# KUBODriver_DC.net
KiCad netlist of a schematic drawn in Altium Designer
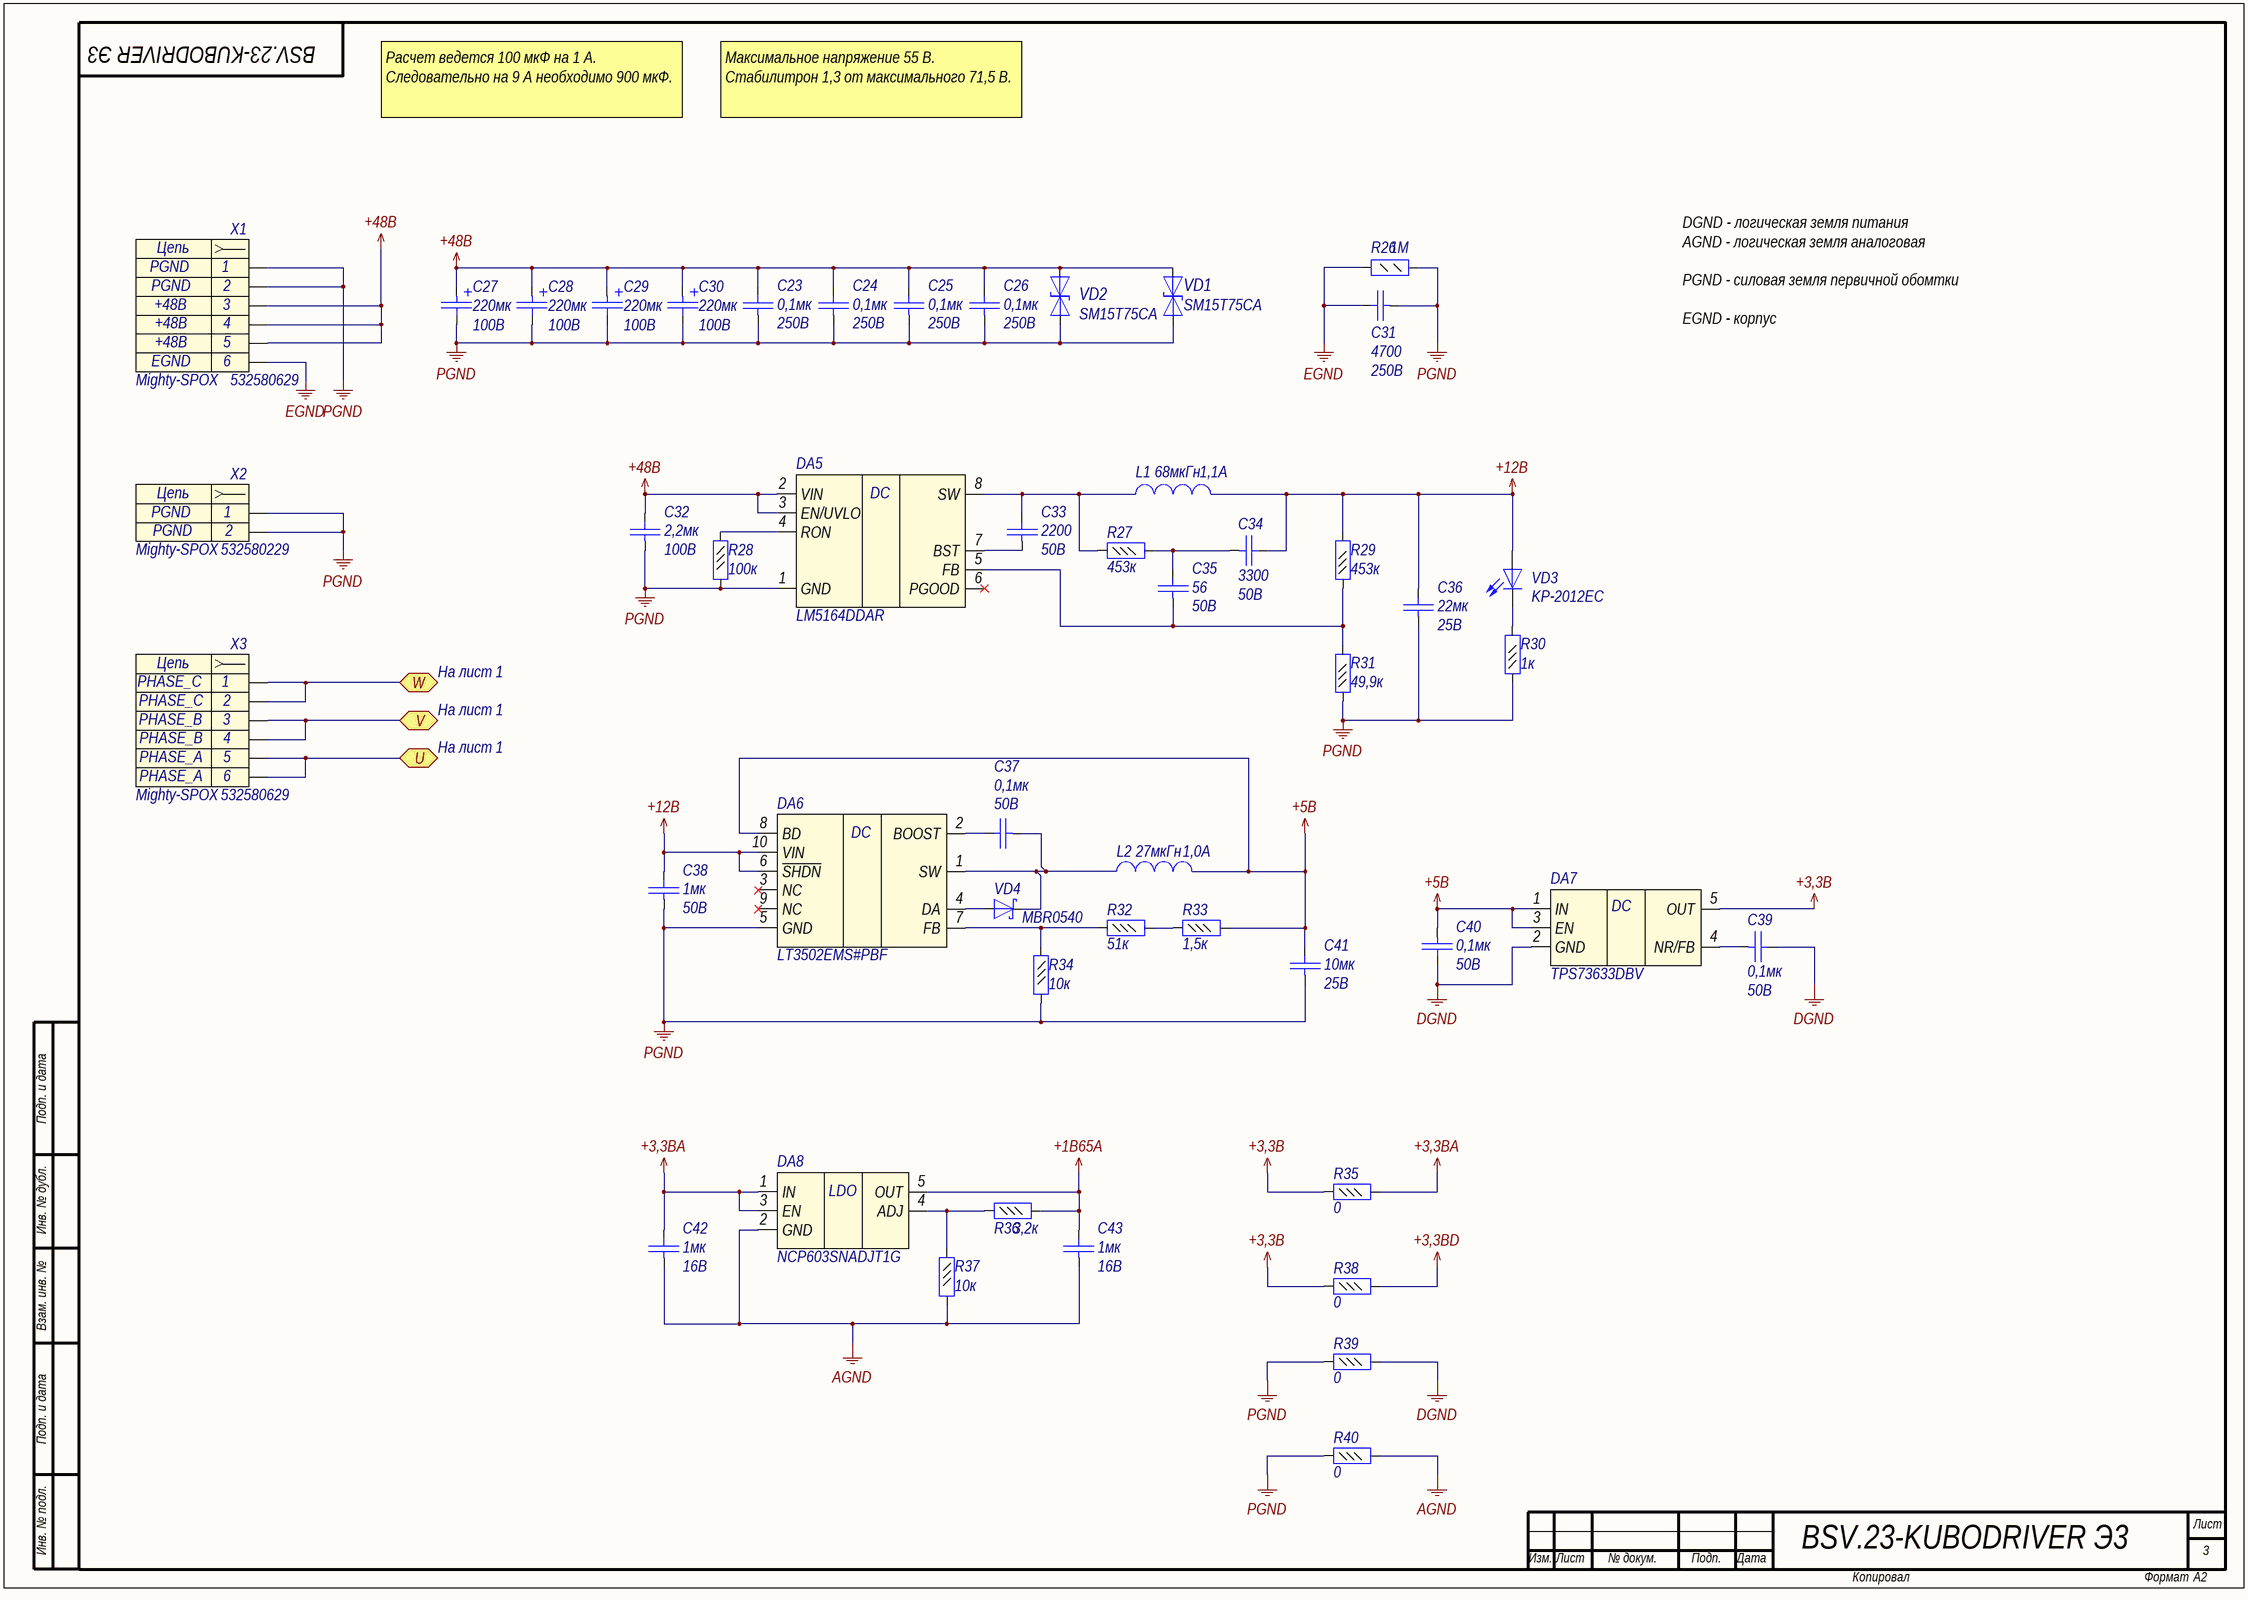
[diagram p0: KUBODriver_DC.SchDoc]

(export (version "E")
  (design (tool "Eeschema 10.0.6"))
  (components
    (comp (ref "C23")
      (value "0,1мк")
      (footprint "C1206")
      (description "Конденсатор")
      (fields
        (field (name "VOLTAGE") "250В")
        (field (name "PART NUMBER") "GRM31CR72E104K")
        (field (name "Comment") "Capacitor")
      )
      (libsource (lib "MOP44") (part "Capacitor"))
    )
    (comp (ref "C24")
      (value "0,1мк")
      (footprint "C1206")
      (description "Конденсатор")
      (fields
        (field (name "VOLTAGE") "250В")
        (field (name "PART NUMBER") "GRM31CR72E104K")
        (field (name "Comment") "Capacitor")
      )
      (libsource (lib "MOP44") (part "Capacitor"))
    )
    (comp (ref "C25")
      (value "0,1мк")
      (footprint "C1206")
      (description "Конденсатор")
      (fields
        (field (name "VOLTAGE") "250В")
        (field (name "PART NUMBER") "GRM31CR72E104K")
        (field (name "Comment") "Capacitor")
      )
      (libsource (lib "MOP44") (part "Capacitor"))
    )
    (comp (ref "C26")
      (value "0,1мк")
      (footprint "C1206")
      (description "Конденсатор")
      (fields
        (field (name "VOLTAGE") "250В")
        (field (name "PART NUMBER") "GRM31CR72E104K")
        (field (name "Comment") "Capacitor")
      )
      (libsource (lib "MOP44") (part "Capacitor"))
    )
    (comp (ref "C27")
      (value "220мк")
      (footprint "K50-35(12.5X25)_V")
      (description "Конденсатор полярный")
      (fields
        (field (name "VOLTAGE") "100B")
        (field (name "PART NUMBER") "B41851A9227M000")
        (field (name "Comment") "Capacitor_pol")
      )
      (libsource (lib "MOP44") (part "Capacitor_pol"))
    )
    (comp (ref "C28")
      (value "220мк")
      (footprint "K50-35(12.5X25)_V")
      (description "Конденсатор полярный")
      (fields
        (field (name "VOLTAGE") "100B")
        (field (name "PART NUMBER") "B41851A9227M000")
        (field (name "Comment") "Capacitor_pol")
      )
      (libsource (lib "MOP44") (part "Capacitor_pol"))
    )
    (comp (ref "C29")
      (value "220мк")
      (footprint "K50-35(12.5X25)_V")
      (description "Конденсатор полярный")
      (fields
        (field (name "VOLTAGE") "100B")
        (field (name "PART NUMBER") "B41851A9227M000")
        (field (name "Comment") "Capacitor_pol")
      )
      (libsource (lib "MOP44") (part "Capacitor_pol"))
    )
    (comp (ref "C30")
      (value "220мк")
      (footprint "K50-35(12.5X25)_V")
      (description "Конденсатор полярный")
      (fields
        (field (name "VOLTAGE") "100B")
        (field (name "PART NUMBER") "B41851A9227M000")
        (field (name "Comment") "Capacitor_pol")
      )
      (libsource (lib "MOP44") (part "Capacitor_pol"))
    )
    (comp (ref "C31")
      (value "4700")
      (footprint "C0805")
      (description "Конденсатор")
      (fields
        (field (name "VOLTAGE") "250В")
        (field (name "PART NUMBER") "GRM21AR72E472KW")
        (field (name "Comment") "Capacitor")
      )
      (libsource (lib "MOP44") (part "Capacitor"))
    )
    (comp (ref "C32")
      (value "2,2мк")
      (footprint "C1210")
      (description "Конденсатор")
      (fields (field (name "VOLTAGE") "100В") (field (name "PART NUMBER") "GCJ32DR72A225KA01L"))
      (libsource (lib "MOP44") (part "Capacitor"))
    )
    (comp (ref "C33")
      (value "2200")
      (footprint "C0402")
      (description "Конденсатор")
      (fields
        (field (name "VOLTAGE") "50B")
        (field (name "PART NUMBER") "GRM155R71H222K")
        (field (name "Comment") "Capacitor")
      )
      (libsource (lib "MOP44") (part "Capacitor"))
    )
    (comp (ref "C34")
      (value "3300")
      (footprint "C0402")
      (description "Конденсатор")
      (fields
        (field (name "VOLTAGE") "50В")
        (field (name "PART NUMBER") "GRM155R71H332KA01D ")
        (field (name "Comment") "Capacitor")
      )
      (libsource (lib "MOP44") (part "Capacitor"))
    )
    (comp (ref "C35")
      (value "56")
      (footprint "C0402")
      (description "Конденсатор")
      (fields
        (field (name "VOLTAGE") "50B")
        (field (name "PART NUMBER") "GRM1555C1H560J*")
        (field (name "Comment") "Capacitor")
      )
      (libsource (lib "MOP44") (part "Capacitor"))
    )
    (comp (ref "C36")
      (value "22мк")
      (footprint "C1210")
      (description "Конденсатор")
      (fields
        (field (name "VOLTAGE") "25B")
        (field (name "PART NUMBER") "TMK325B7226KMHT")
        (field (name "Comment") "Capacitor")
      )
      (libsource (lib "MOP44") (part "Capacitor"))
    )
    (comp (ref "C37")
      (value "0,1мк")
      (footprint "C0402")
      (description "Конденсатор")
      (fields
        (field (name "VOLTAGE") "50В")
        (field (name "PART NUMBER") "GRM155R71H104KE14D ")
        (field (name "Comment") "Capacitor")
      )
      (libsource (lib "MOP44") (part "Capacitor"))
    )
    (comp (ref "C38")
      (value "1мк")
      (footprint "C0805")
      (description "Конденсатор")
      (fields
        (field (name "VOLTAGE") "50B")
        (field (name "PART NUMBER") "GRM21BR71H105K")
        (field (name "Comment") "Capacitor")
      )
      (libsource (lib "MOP44") (part "Capacitor"))
    )
    (comp (ref "C39")
      (value "0,1мк")
      (footprint "C0402")
      (description "Конденсатор")
      (fields
        (field (name "VOLTAGE") "50В")
        (field (name "PART NUMBER") "GRM155R71H104KE14D ")
        (field (name "Comment") "Capacitor")
      )
      (libsource (lib "MOP44") (part "Capacitor"))
    )
    (comp (ref "C40")
      (value "0,1мк")
      (footprint "C0402")
      (description "Конденсатор")
      (fields
        (field (name "VOLTAGE") "50В")
        (field (name "PART NUMBER") "GRM155R71H104KE14D ")
        (field (name "Comment") "Capacitor")
      )
      (libsource (lib "MOP44") (part "Capacitor"))
    )
    (comp (ref "C41")
      (value "10мк")
      (footprint "C1206")
      (description "Конденсатор")
      (fields
        (field (name "VOLTAGE") "25В")
        (field (name "PART NUMBER") "GRM31CR71E106KA12L*")
        (field (name "Comment") "Capacitor")
      )
      (libsource (lib "MOP44") (part "Capacitor"))
    )
    (comp (ref "C42")
      (value "1мк")
      (footprint "C0603")
      (description "Конденсатор")
      (fields
        (field (name "VOLTAGE") "16B")
        (field (name "PART NUMBER") "GRM188R71C105KA12D**")
        (field (name "Comment") "Capacitor")
      )
      (libsource (lib "MOP44") (part "Capacitor"))
    )
    (comp (ref "C43")
      (value "1мк")
      (footprint "C0603")
      (description "Конденсатор")
      (fields
        (field (name "VOLTAGE") "16B")
        (field (name "PART NUMBER") "GRM188R71C105KA12D**")
        (field (name "Comment") "Capacitor")
      )
      (libsource (lib "MOP44") (part "Capacitor"))
    )
    (comp (ref "DA5")
      (value "LM5164")
      (footprint "SO Powerpad8")
      (description "1-A synchronous buck DC/DC converter with ultra-low IQ")
      (fields (field (name "PART NUMBER") "LM5164DDAR") (field (name "MANUFACTURER") "Texas Instruments"))
      (libsource (lib "MOP44") (part "LM5164"))
    )
    (comp (ref "DA6")
      (value "LT3502_MS")
      (footprint "MSOP10")
      (description "1.1MHz/2.2MHz, 500mA  Step-Down Regulators")
      (fields (field (name "PART NUMBER") "LT3502EMS#PBF") (field (name "MANUFACTURER") "Linear Technology"))
      (libsource (lib "MOP44") (part "LT3502_MS"))
    )
    (comp (ref "DA7")
      (value "TPS736DBV")
      (footprint "SOT23-5")
      (description "400-mA Low-Dropout Regulator with Reverse Current  Protection")
      (fields (field (name "PART NUMBER") "TPS73633DBV") (field (name "MANUFACTURER") "Texas Instruments"))
      (libsource (lib "MOP44") (part "TPS736DBV"))
    )
    (comp (ref "DA8")
      (value "NCP603")
      (footprint "TSOP5")
      (description "High Performance  CMOS LDO Regulator with  Enable and Enhanced ESD  Protection")
      (fields (field (name "PART NUMBER") "NCP603SNADJT1G") (field (name "MANUFACTURER") "ON Semiconductor"))
      (libsource (lib "MOP44") (part "NCP603"))
    )
    (comp (ref "L1")
      (value "68мкГн")
      (footprint "SDR1006")
      (description "EMI Suppression Filter")
      (fields
        (field (name "RATED CURRENT") "1,1A")
        (field (name "PART NUMBER") "SDR1006- 680KL")
        (field (name "Comment") "Inductor")
      )
      (libsource (lib "MOP44") (part "Inductor"))
    )
    (comp (ref "L2")
      (value "27мкГн")
      (footprint "SDR0604")
      (description "EMI Suppression Filter")
      (fields
        (field (name "RATED CURRENT") "1,0A")
        (field (name "PART NUMBER") "SDR0604- 270YL")
        (field (name "Comment") "Inductor")
      )
      (libsource (lib "MOP44") (part "Inductor"))
    )
    (comp (ref "R26")
      (value "1М")
      (footprint "R0805")
      (description "Резистор")
      (fields (field (name "PART NUMBER") "RC0805FR-071ML") (field (name "POWER") "0,125Вт"))
      (libsource (lib "MOP44") (part "Resistor_0,125Вт"))
    )
    (comp (ref "R27")
      (value "453к")
      (footprint "R0402")
      (description "Резистор")
      (fields (field (name "PART NUMBER") "RC0402FR-07453KL") (field (name "POWER") "0,062Вт"))
      (libsource (lib "MOP44") (part "Resistor_0,062Вт"))
    )
    (comp (ref "R28")
      (value "100к")
      (footprint "R0402")
      (description "Резистор")
      (fields (field (name "PART NUMBER") "RC0402FR-07100KL") (field (name "POWER") "0,062Вт"))
      (libsource (lib "") (part "Resistor_0,062Вт_1"))
    )
    (comp (ref "R29")
      (value "453к")
      (footprint "R0402")
      (description "Резистор")
      (fields (field (name "PART NUMBER") "RC0402FR-07453KL") (field (name "POWER") "0,062Вт"))
      (libsource (lib "") (part "Resistor_0,062Вт_2"))
    )
    (comp (ref "R30")
      (value "1к")
      (footprint "R0402")
      (description "Резистор")
      (fields (field (name "PART NUMBER") "RC0402FR-071KL") (field (name "POWER") "0,062Вт"))
      (libsource (lib "") (part "Resistor_0,062Вт_2"))
    )
    (comp (ref "R31")
      (value "49,9к")
      (footprint "R0402")
      (description "Резистор")
      (fields (field (name "PART NUMBER") "RC0402FR-0749K9L") (field (name "POWER") "0,062Вт"))
      (libsource (lib "") (part "Resistor_0,062Вт_2"))
    )
    (comp (ref "R32")
      (value "51к")
      (footprint "R0402")
      (description "Резистор")
      (fields (field (name "PART NUMBER") "RC0402FR-0751KL") (field (name "POWER") "0,062Вт"))
      (libsource (lib "MOP44") (part "Resistor_0,062Вт"))
    )
    (comp (ref "R33")
      (value "1,5к")
      (footprint "R0402")
      (description "Резистор")
      (fields (field (name "PART NUMBER") "RC0402FR-071K5") (field (name "POWER") "0,062Вт"))
      (libsource (lib "MOP44") (part "Resistor_0,062Вт"))
    )
    (comp (ref "R34")
      (value "10к")
      (footprint "R0402")
      (description "Резистор")
      (fields (field (name "PART NUMBER") "RC0402FR-0710KL") (field (name "POWER") "0,062Вт"))
      (libsource (lib "") (part "Resistor_0,062Вт_1"))
    )
    (comp (ref "R35")
      (value "0")
      (footprint "R0603")
      (description "Резистор")
      (fields (field (name "PART NUMBER") "RC0603FR-070RL") (field (name "POWER") "0,062Вт"))
      (libsource (lib "MOP44") (part "Resistor_0,062Вт"))
    )
    (comp (ref "R36")
      (value "3,2к")
      (footprint "R0402")
      (description "Резистор")
      (fields (field (name "PART NUMBER") "RT0402BRD073K2L") (field (name "POWER") "0,062Вт"))
      (libsource (lib "MOP44") (part "Resistor_0,062Вт"))
    )
    (comp (ref "R37")
      (value "10к")
      (footprint "R0402")
      (description "Резистор")
      (fields (field (name "PART NUMBER") "RC0402FR-0710KL") (field (name "POWER") "0,062Вт"))
      (libsource (lib "") (part "Resistor_0,062Вт_1"))
    )
    (comp (ref "R38")
      (value "0")
      (footprint "R0603")
      (description "Резистор")
      (fields (field (name "PART NUMBER") "RC0603FR-070RL") (field (name "POWER") "0,062Вт"))
      (libsource (lib "MOP44") (part "Resistor_0,062Вт"))
    )
    (comp (ref "R39")
      (value "0")
      (footprint "R0603")
      (description "Резистор")
      (fields (field (name "PART NUMBER") "RC0603FR-070RL") (field (name "POWER") "0,062Вт"))
      (libsource (lib "MOP44") (part "Resistor_0,062Вт"))
    )
    (comp (ref "R40")
      (value "0")
      (footprint "R0603")
      (description "Резистор")
      (fields (field (name "PART NUMBER") "RC0603FR-070RL") (field (name "POWER") "0,062Вт"))
      (libsource (lib "MOP44") (part "Resistor_0,062Вт"))
    )
    (comp (ref "VD1")
      (value "DiodeZenerDual")
      (footprint "SMC")
      (description "Cтабилитрон (диод выпрямительный лавинный) двусторонний")
      (fields (field (name "PART NUMBER") "SM15T75CA"))
      (libsource (lib "MOP44") (part "DiodeZenerDual"))
    )
    (comp (ref "VD2")
      (value "DiodeZenerDual")
      (footprint "SMC")
      (description "Cтабилитрон (диод выпрямительный лавинный) двусторонний")
      (fields (field (name "PART NUMBER") "SM15T75CA"))
      (libsource (lib "MOP44") (part "DiodeZenerDual"))
    )
    (comp (ref "VD3")
      (value "LED")
      (footprint "L_0805")
      (description "Светодиод")
      (fields (field (name "PART NUMBER") "KP-2012EC"))
      (libsource (lib "MOP44") (part "LED"))
    )
    (comp (ref "VD4")
      (value "DiodeSchottky")
      (footprint "SOD-123")
      (description "Диод Шоттки")
      (fields (field (name "PART NUMBER") "MBR0540"))
      (libsource (lib "MOP44") (part "DiodeSchottky"))
    )
    (comp (ref "X1")
      (value "Header_6_sct")
      (footprint "MOLEX_532580629")
      (description "Разъем - 6 конт. розетка")
      (fields (field (name "PART NAME") "Mighty-SPOX") (field (name "PART NUMBER") "532580629"))
      (libsource (lib "MOP44") (part "Header_6_sct"))
    )
    (comp (ref "X2")
      (value "Header_2_sct")
      (footprint "MOLEX_532580229")
      (description "Разъем - 2 конт. розетка")
      (fields (field (name "PART NAME") "Mighty-SPOX") (field (name "PART NUMBER") "532580229"))
      (libsource (lib "MOP44") (part "Header_2_sct"))
    )
    (comp (ref "X3")
      (value "Header_6_sct")
      (footprint "MOLEX_532580629")
      (description "Разъем - 6 конт. розетка")
      (fields (field (name "PART NAME") "Mighty-SPOX") (field (name "PART NUMBER") "532580629"))
      (libsource (lib "MOP44") (part "Header_6_sct"))
    )
  )
  (nets
    (net (code "1") (name "+1B65A") (class "Default")
      (node (ref "C43") (pin "2") (pinfunction "2_2") (pintype "passive"))
      (node (ref "DA8") (pin "5") (pinfunction "OUT_5") (pintype "power_in"))
      (node (ref "R36") (pin "2") (pinfunction "2_2") (pintype "passive"))
    )
    (net (code "2") (name "+3,3B") (class "Default")
      (node (ref "DA7") (pin "5") (pinfunction "OUT_5") (pintype "power_in"))
      (node (ref "R35") (pin "1") (pinfunction "1_1") (pintype "passive"))
      (node (ref "R38") (pin "1") (pinfunction "1_1") (pintype "passive"))
    )
    (net (code "3") (name "+3,3BA") (class "Default")
      (node (ref "C42") (pin "2") (pinfunction "2_2") (pintype "passive"))
      (node (ref "DA8") (pin "1") (pinfunction "IN_1") (pintype "power_in"))
      (node (ref "DA8") (pin "3") (pinfunction "EN_3") (pintype "power_in"))
      (node (ref "R35") (pin "2") (pinfunction "2_2") (pintype "passive"))
    )
    (net (code "4") (name "+3,3BD") (class "Default")
      (node (ref "R38") (pin "2") (pinfunction "2_2") (pintype "passive"))
    )
    (net (code "5") (name "+5B") (class "Default")
      (node (ref "C40") (pin "1") (pinfunction "1_1") (pintype "passive"))
      (node (ref "C41") (pin "2") (pinfunction "2_2") (pintype "passive"))
      (node (ref "DA6") (pin "8") (pinfunction "BD_8") (pintype "power_in"))
      (node (ref "DA7") (pin "1") (pinfunction "IN_1") (pintype "power_in"))
      (node (ref "DA7") (pin "3") (pinfunction "EN_3") (pintype "power_in"))
      (node (ref "L2") (pin "2") (pinfunction "2_2") (pintype "passive"))
      (node (ref "R33") (pin "2") (pinfunction "2_2") (pintype "passive"))
    )
    (net (code "6") (name "+12B") (class "Default")
      (node (ref "C34") (pin "2") (pinfunction "2_2") (pintype "passive"))
      (node (ref "C36") (pin "2") (pinfunction "2_2") (pintype "passive"))
      (node (ref "C38") (pin "2") (pinfunction "2_2") (pintype "passive"))
      (node (ref "DA6") (pin "10") (pinfunction "VIN_10") (pintype "power_in"))
      (node (ref "DA6") (pin "6") (pinfunction "~{SHDN}_6") (pintype "power_in"))
      (node (ref "L1") (pin "2") (pinfunction "2_2") (pintype "passive"))
      (node (ref "R29") (pin "2") (pinfunction "2_2") (pintype "passive"))
      (node (ref "VD3") (pin "2") (pinfunction "A_2") (pintype "passive"))
    )
    (net (code "7") (name "+48B") (class "Default")
      (node (ref "C23") (pin "2") (pinfunction "2_2") (pintype "passive"))
      (node (ref "C24") (pin "2") (pinfunction "2_2") (pintype "passive"))
      (node (ref "C25") (pin "2") (pinfunction "2_2") (pintype "passive"))
      (node (ref "C26") (pin "2") (pinfunction "2_2") (pintype "passive"))
      (node (ref "C27") (pin "1") (pinfunction "1_1") (pintype "passive"))
      (node (ref "C28") (pin "1") (pinfunction "1_1") (pintype "passive"))
      (node (ref "C29") (pin "1") (pinfunction "1_1") (pintype "passive"))
      (node (ref "C30") (pin "1") (pinfunction "1_1") (pintype "passive"))
      (node (ref "C32") (pin "2") (pinfunction "2_2") (pintype "passive"))
      (node (ref "DA5") (pin "2") (pinfunction "VIN_2") (pintype "power_in"))
      (node (ref "DA5") (pin "3") (pinfunction "EN/UVLO_3") (pintype "power_in"))
      (node (ref "VD1") (pin "1") (pinfunction "K_1") (pintype "passive"))
      (node (ref "VD2") (pin "2") (pinfunction "A_2") (pintype "passive"))
      (node (ref "X1") (pin "3") (pinfunction "3_3") (pintype "passive"))
      (node (ref "X1") (pin "4") (pinfunction "4_4") (pintype "passive"))
      (node (ref "X1") (pin "5") (pinfunction "5_5") (pintype "passive"))
    )
    (net (code "8") (name "/U") (class "Default")
      (node (ref "X3") (pin "5") (pinfunction "5_5") (pintype "passive"))
      (node (ref "X3") (pin "6") (pinfunction "6_6") (pintype "passive"))
    )
    (net (code "9") (name "/V") (class "Default")
      (node (ref "X3") (pin "3") (pinfunction "3_3") (pintype "passive"))
      (node (ref "X3") (pin "4") (pinfunction "4_4") (pintype "passive"))
    )
    (net (code "10") (name "/W") (class "Default")
      (node (ref "X3") (pin "1") (pinfunction "1_1") (pintype "passive"))
      (node (ref "X3") (pin "2") (pinfunction "2_2") (pintype "passive"))
    )
    (net (code "11") (name "AGND") (class "Default")
      (node (ref "C42") (pin "1") (pinfunction "1_1") (pintype "passive"))
      (node (ref "C43") (pin "1") (pinfunction "1_1") (pintype "passive"))
      (node (ref "DA8") (pin "2") (pinfunction "GND_2") (pintype "power_in"))
      (node (ref "R37") (pin "2") (pinfunction "2_2") (pintype "passive"))
      (node (ref "R40") (pin "2") (pinfunction "2_2") (pintype "passive"))
    )
    (net (code "12") (name "DGND") (class "Default")
      (node (ref "C39") (pin "2") (pinfunction "2_2") (pintype "passive"))
      (node (ref "C40") (pin "2") (pinfunction "2_2") (pintype "passive"))
      (node (ref "DA7") (pin "2") (pinfunction "GND_2") (pintype "power_in"))
      (node (ref "R39") (pin "2") (pinfunction "2_2") (pintype "passive"))
    )
    (net (code "13") (name "EGND") (class "Default")
      (node (ref "C31") (pin "2") (pinfunction "2_2") (pintype "passive"))
      (node (ref "R26") (pin "2") (pinfunction "2_2") (pintype "passive"))
      (node (ref "X1") (pin "6") (pinfunction "6_6") (pintype "passive"))
    )
    (net (code "14") (name "Net-(C34-Pad1)") (class "Default")
      (node (ref "C34") (pin "1") (pinfunction "1_1") (pintype "passive"))
      (node (ref "C35") (pin "2") (pinfunction "2_2") (pintype "passive"))
      (node (ref "R27") (pin "2") (pinfunction "2_2") (pintype "passive"))
    )
    (net (code "15") (name "Net-(DA5-BST)") (class "Default")
      (node (ref "C33") (pin "1") (pinfunction "1_1") (pintype "passive"))
      (node (ref "DA5") (pin "7") (pinfunction "BST_7") (pintype "power_in"))
    )
    (net (code "16") (name "Net-(DA5-FB)") (class "Default")
      (node (ref "C35") (pin "1") (pinfunction "1_1") (pintype "passive"))
      (node (ref "DA5") (pin "5") (pinfunction "FB_5") (pintype "power_in"))
      (node (ref "R29") (pin "1") (pinfunction "1_1") (pintype "passive"))
      (node (ref "R31") (pin "2") (pinfunction "2_2") (pintype "passive"))
    )
    (net (code "17") (name "Net-(DA5-RON)") (class "Default")
      (node (ref "DA5") (pin "4") (pinfunction "RON_4") (pintype "power_in"))
      (node (ref "R28") (pin "1") (pinfunction "1_1") (pintype "passive"))
    )
    (net (code "18") (name "Net-(DA5-SW)") (class "Default")
      (node (ref "C33") (pin "2") (pinfunction "2_2") (pintype "passive"))
      (node (ref "DA5") (pin "8") (pinfunction "SW_8") (pintype "power_in"))
      (node (ref "L1") (pin "1") (pinfunction "1_1") (pintype "passive"))
      (node (ref "R27") (pin "1") (pinfunction "1_1") (pintype "passive"))
    )
    (net (code "19") (name "Net-(DA6-BOOST)") (class "Default")
      (node (ref "C37") (pin "2") (pinfunction "2_2") (pintype "passive"))
      (node (ref "DA6") (pin "2") (pinfunction "BOOST_2") (pintype "power_in"))
    )
    (net (code "20") (name "Net-(DA6-DA)") (class "Default")
      (node (ref "DA6") (pin "4") (pinfunction "DA_4") (pintype "power_in"))
      (node (ref "VD4") (pin "2") (pinfunction "A_2") (pintype "passive"))
    )
    (net (code "21") (name "Net-(DA6-FB)") (class "Default")
      (node (ref "DA6") (pin "7") (pinfunction "FB_7") (pintype "power_in"))
      (node (ref "R32") (pin "1") (pinfunction "1_1") (pintype "passive"))
      (node (ref "R34") (pin "1") (pinfunction "1_1") (pintype "passive"))
    )
    (net (code "22") (name "Net-(DA6-SW)") (class "Default")
      (node (ref "C37") (pin "1") (pinfunction "1_1") (pintype "passive"))
      (node (ref "DA6") (pin "1") (pinfunction "SW_1") (pintype "power_in"))
      (node (ref "L2") (pin "1") (pinfunction "1_1") (pintype "passive"))
      (node (ref "VD4") (pin "1") (pinfunction "K_1") (pintype "passive"))
    )
    (net (code "23") (name "Net-(DA7-NR{slash}FB)") (class "Default")
      (node (ref "C39") (pin "1") (pinfunction "1_1") (pintype "passive"))
      (node (ref "DA7") (pin "4") (pinfunction "NR/FB_4") (pintype "power_in"))
    )
    (net (code "24") (name "Net-(DA8-ADJ)") (class "Default")
      (node (ref "DA8") (pin "4") (pinfunction "ADJ_4") (pintype "power_in"))
      (node (ref "R36") (pin "1") (pinfunction "1_1") (pintype "passive"))
      (node (ref "R37") (pin "1") (pinfunction "1_1") (pintype "passive"))
    )
    (net (code "25") (name "Net-(R32-Pad2)") (class "Default")
      (node (ref "R32") (pin "2") (pinfunction "2_2") (pintype "passive"))
      (node (ref "R33") (pin "1") (pinfunction "1_1") (pintype "passive"))
    )
    (net (code "26") (name "Net-(VD3-K)") (class "Default")
      (node (ref "R30") (pin "2") (pinfunction "2_2") (pintype "passive"))
      (node (ref "VD3") (pin "1") (pinfunction "K_1") (pintype "passive"))
    )
    (net (code "27") (name "PGND") (class "Default")
      (node (ref "C23") (pin "1") (pinfunction "1_1") (pintype "passive"))
      (node (ref "C24") (pin "1") (pinfunction "1_1") (pintype "passive"))
      (node (ref "C25") (pin "1") (pinfunction "1_1") (pintype "passive"))
      (node (ref "C26") (pin "1") (pinfunction "1_1") (pintype "passive"))
      (node (ref "C27") (pin "2") (pinfunction "2_2") (pintype "passive"))
      (node (ref "C28") (pin "2") (pinfunction "2_2") (pintype "passive"))
      (node (ref "C29") (pin "2") (pinfunction "2_2") (pintype "passive"))
      (node (ref "C30") (pin "2") (pinfunction "2_2") (pintype "passive"))
      (node (ref "C31") (pin "1") (pinfunction "1_1") (pintype "passive"))
      (node (ref "C32") (pin "1") (pinfunction "1_1") (pintype "passive"))
      (node (ref "C36") (pin "1") (pinfunction "1_1") (pintype "passive"))
      (node (ref "C38") (pin "1") (pinfunction "1_1") (pintype "passive"))
      (node (ref "C41") (pin "1") (pinfunction "1_1") (pintype "passive"))
      (node (ref "DA5") (pin "1") (pinfunction "GND_1") (pintype "power_in"))
      (node (ref "DA6") (pin "5") (pinfunction "GND_5") (pintype "power_in"))
      (node (ref "R26") (pin "1") (pinfunction "1_1") (pintype "passive"))
      (node (ref "R28") (pin "2") (pinfunction "2_2") (pintype "passive"))
      (node (ref "R30") (pin "1") (pinfunction "1_1") (pintype "passive"))
      (node (ref "R31") (pin "1") (pinfunction "1_1") (pintype "passive"))
      (node (ref "R34") (pin "2") (pinfunction "2_2") (pintype "passive"))
      (node (ref "R39") (pin "1") (pinfunction "1_1") (pintype "passive"))
      (node (ref "R40") (pin "1") (pinfunction "1_1") (pintype "passive"))
      (node (ref "VD1") (pin "2") (pinfunction "A_2") (pintype "passive"))
      (node (ref "VD2") (pin "1") (pinfunction "K_1") (pintype "passive"))
      (node (ref "X1") (pin "1") (pinfunction "1_1") (pintype "passive"))
      (node (ref "X1") (pin "2") (pinfunction "2_2") (pintype "passive"))
      (node (ref "X2") (pin "1") (pinfunction "1_1") (pintype "passive"))
      (node (ref "X2") (pin "2") (pinfunction "2_2") (pintype "passive"))
    )
    (net (code "28") (name "unconnected-(DA5-PGOOD-Pad6)") (class "Default")
      (node (ref "DA5") (pin "6") (pinfunction "PGOOD_6") (pintype "power_in+no_connect"))
    )
    (net (code "29") (name "unconnected-(DA6-NC-Pad3)") (class "Default")
      (node (ref "DA6") (pin "3") (pinfunction "NC_3") (pintype "power_in+no_connect"))
    )
    (net (code "30") (name "unconnected-(DA6-NC-Pad9)") (class "Default")
      (node (ref "DA6") (pin "9") (pinfunction "NC_9") (pintype "power_in+no_connect"))
    )
  )
)
